# ReflowController_v1_3.net
KiCad netlist of a schematic drawn in EAGLE
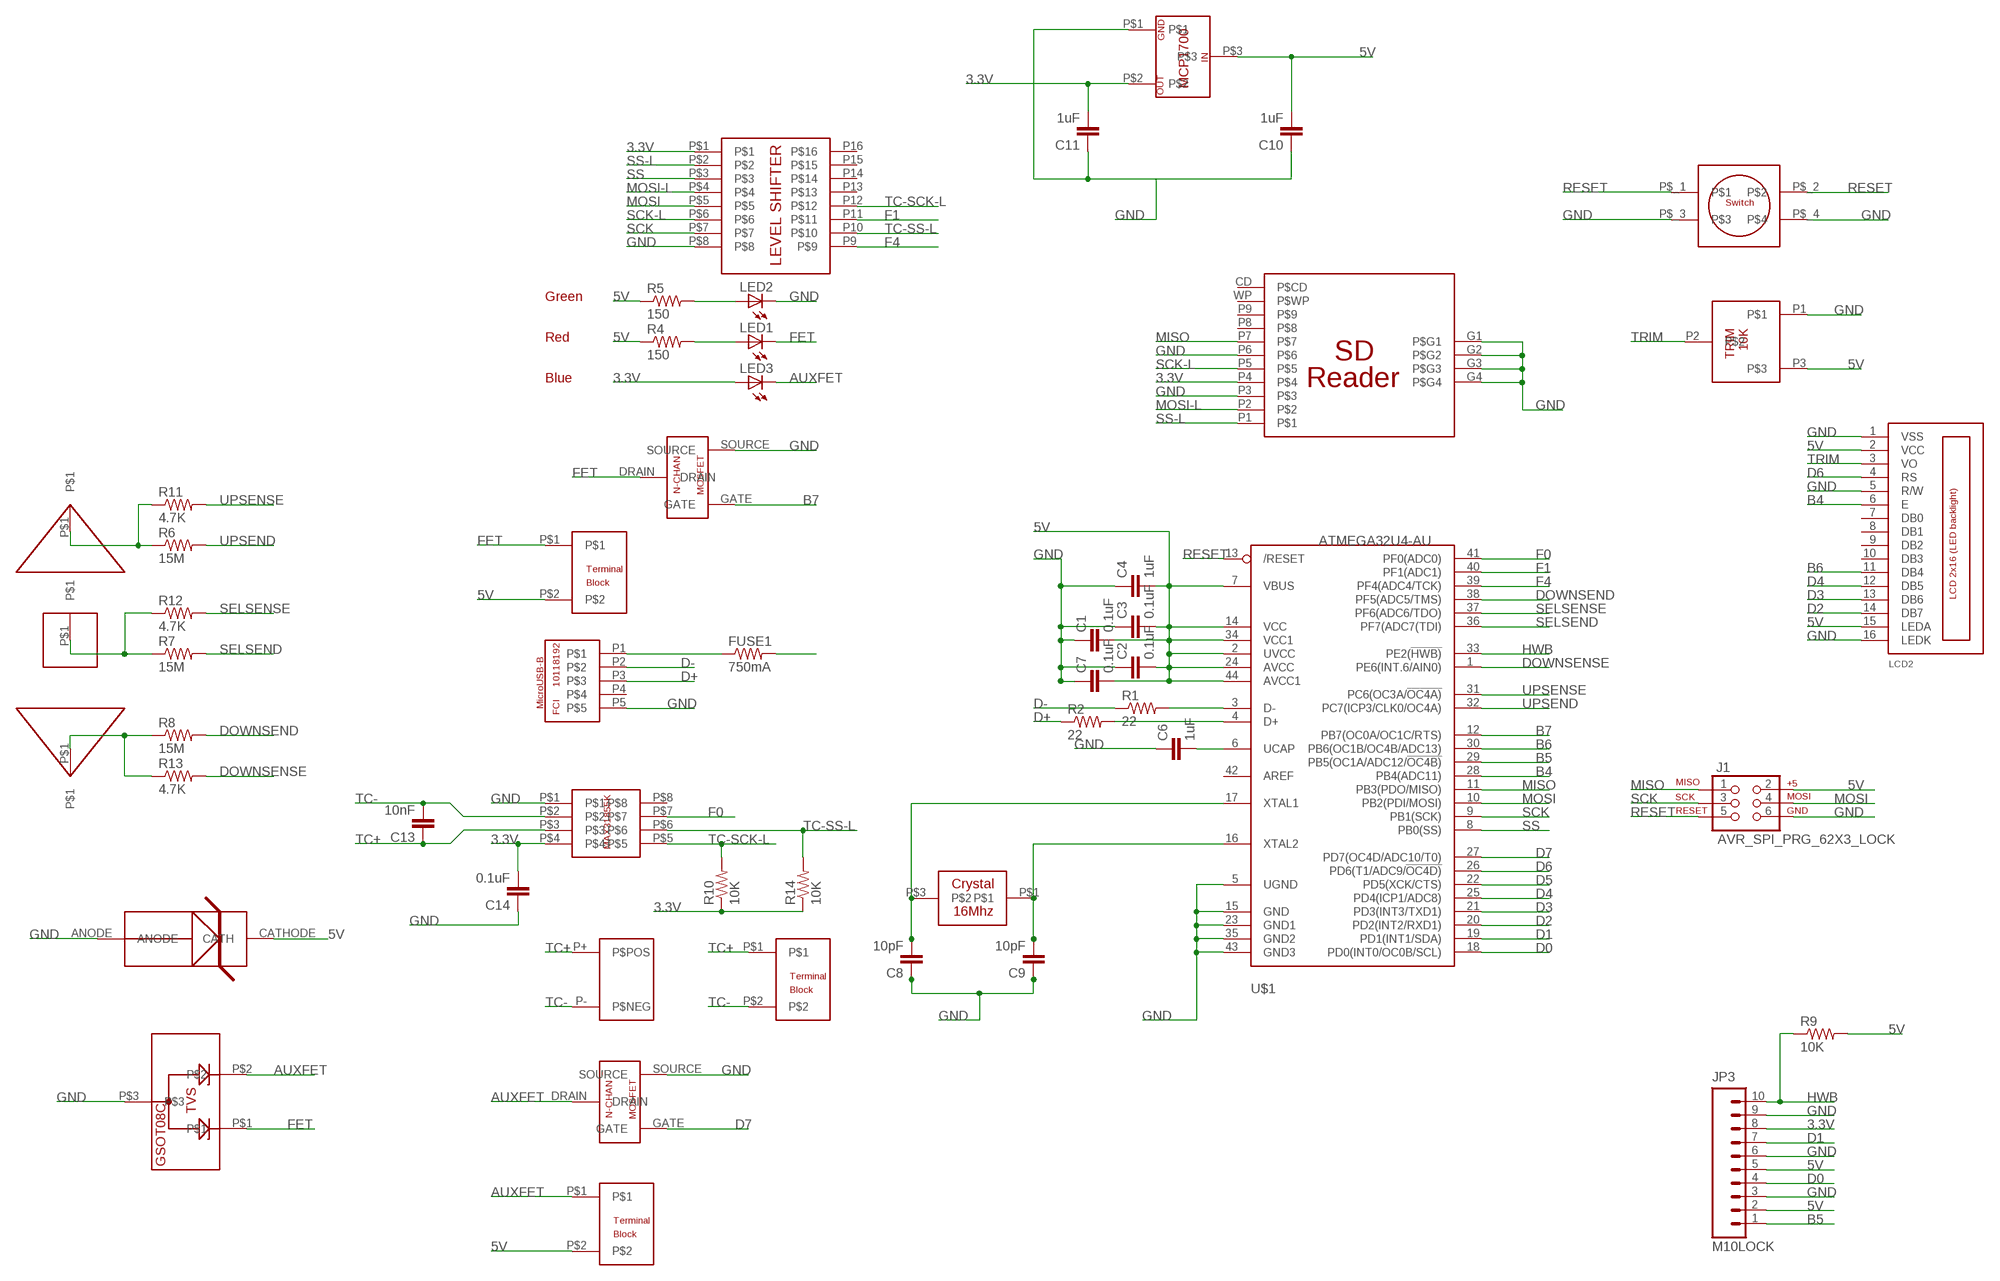
[diagram p0: schematic, sheet 1]

(export (version "E")
  (design (tool "Eeschema 10.0.6"))
  (components
    (comp (ref "C1")
      (value "0.1uF")
      (footprint "eagle-import:0603-CAP")
      (libsource (lib "eagle-import") (part "CAP0603-CAP"))
    )
    (comp (ref "C2")
      (value "0.1uF")
      (footprint "eagle-import:0603-CAP")
      (libsource (lib "eagle-import") (part "CAP0603-CAP"))
    )
    (comp (ref "C3")
      (value "0.1uF")
      (footprint "eagle-import:0603-CAP")
      (libsource (lib "eagle-import") (part "CAP0603-CAP"))
    )
    (comp (ref "C4")
      (value "1uF")
      (footprint "eagle-import:0603-CAP")
      (libsource (lib "eagle-import") (part "CAP0603-CAP"))
    )
    (comp (ref "C6")
      (value "1uF")
      (footprint "eagle-import:0603-CAP")
      (libsource (lib "eagle-import") (part "CAP0603-CAP"))
    )
    (comp (ref "C7")
      (value "0.1uF")
      (footprint "eagle-import:0603-CAP")
      (libsource (lib "eagle-import") (part "CAP0603-CAP"))
    )
    (comp (ref "C8")
      (value "10pF")
      (footprint "eagle-import:0603-CAP")
      (libsource (lib "eagle-import") (part "CAP0603-CAP"))
    )
    (comp (ref "C9")
      (value "10pF")
      (footprint "eagle-import:0603-CAP")
      (libsource (lib "eagle-import") (part "CAP0603-CAP"))
    )
    (comp (ref "C10")
      (value "1uF")
      (footprint "eagle-import:0603-CAP")
      (libsource (lib "eagle-import") (part "CAP0603-CAP"))
    )
    (comp (ref "C11")
      (value "1uF")
      (footprint "eagle-import:0603-CAP")
      (libsource (lib "eagle-import") (part "CAP0603-CAP"))
    )
    (comp (ref "C13")
      (value "10nF")
      (footprint "eagle-import:0603-CAP")
      (libsource (lib "eagle-import") (part "CAP0603-CAP"))
    )
    (comp (ref "C14")
      (value "0.1uF")
      (footprint "eagle-import:0603-CAP")
      (libsource (lib "eagle-import") (part "CAP0603-CAP"))
    )
    (comp (ref "FUSE1")
      (value "750mA")
      (footprint "eagle-import:0603-RES")
      (libsource (lib "eagle-import") (part "RESISTOR0603-RES"))
    )
    (comp (ref "J1")
      (value "AVR_SPI_PRG_62X3_LOCK")
      (footprint "eagle-import:2X3_LOCK")
      (libsource (lib "eagle-import") (part "AVR_SPI_PRG_62X3_LOCK"))
    )
    (comp (ref "JP3")
      (value "M10LOCK")
      (footprint "eagle-import:1X10_LOCK")
      (libsource (lib "eagle-import") (part "M10LOCK"))
    )
    (comp (ref "LCD2")
      (value "LCD_2X16_SIL")
      (footprint "eagle-import:HY-1602F")
      (libsource (lib "eagle-import") (part "LCD_2X16_SIL"))
    )
    (comp (ref "LED1")
      (value "LED0603")
      (footprint "eagle-import:LED-0603")
      (libsource (lib "eagle-import") (part "LED0603"))
    )
    (comp (ref "LED2")
      (value "LED0603")
      (footprint "eagle-import:LED-0603")
      (libsource (lib "eagle-import") (part "LED0603"))
    )
    (comp (ref "LED3")
      (value "LED0603")
      (footprint "eagle-import:LED-0603")
      (libsource (lib "eagle-import") (part "LED0603"))
    )
    (comp (ref "R1")
      (value "22")
      (footprint "eagle-import:0603-RES")
      (libsource (lib "eagle-import") (part "RESISTOR0603-RES"))
    )
    (comp (ref "R2")
      (value "22")
      (footprint "eagle-import:0603-RES")
      (libsource (lib "eagle-import") (part "RESISTOR0603-RES"))
    )
    (comp (ref "R4")
      (value "150")
      (footprint "eagle-import:0603-RES")
      (libsource (lib "eagle-import") (part "RESISTOR0603-RES"))
    )
    (comp (ref "R5")
      (value "150")
      (footprint "eagle-import:0603-RES")
      (libsource (lib "eagle-import") (part "RESISTOR0603-RES"))
    )
    (comp (ref "R6")
      (value "15M")
      (footprint "eagle-import:0603-RES")
      (libsource (lib "eagle-import") (part "RESISTOR0603-RES"))
    )
    (comp (ref "R7")
      (value "15M")
      (footprint "eagle-import:0603-RES")
      (libsource (lib "eagle-import") (part "RESISTOR0603-RES"))
    )
    (comp (ref "R8")
      (value "15M")
      (footprint "eagle-import:0603-RES")
      (libsource (lib "eagle-import") (part "RESISTOR0603-RES"))
    )
    (comp (ref "R9")
      (value "10K")
      (footprint "eagle-import:0603-RES")
      (libsource (lib "eagle-import") (part "RESISTOR0603-RES"))
    )
    (comp (ref "R10")
      (value "10K")
      (footprint "eagle-import:0603-RES")
      (libsource (lib "eagle-import") (part "RESISTOR0603-RES"))
    )
    (comp (ref "R11")
      (value "4.7K")
      (footprint "eagle-import:0603-RES")
      (libsource (lib "eagle-import") (part "RESISTOR0603-RES"))
    )
    (comp (ref "R12")
      (value "4.7K")
      (footprint "eagle-import:0603-RES")
      (libsource (lib "eagle-import") (part "RESISTOR0603-RES"))
    )
    (comp (ref "R13")
      (value "4.7K")
      (footprint "eagle-import:0603-RES")
      (libsource (lib "eagle-import") (part "RESISTOR0603-RES"))
    )
    (comp (ref "R14")
      (value "10K")
      (footprint "eagle-import:0603-RES")
      (libsource (lib "eagle-import") (part "RESISTOR0603-RES"))
    )
    (comp (ref "U$1")
      (value "ATMEGA32U4-AU")
      (footprint "eagle-import:TQFP44")
      (libsource (lib "eagle-import") (part "ATMEGA32U4-AU"))
    )
    (comp (ref "U$2")
      (value "16MHZ-CRYSTAL_NX3225GA-16.000M-STD-CRG-1")
      (footprint "eagle-import:16MHZ-CRYSTAL_NX3225GA-16.000M-STD-CRG-1")
      (libsource (lib "eagle-import") (part "16MHZ-CRYSTAL_NX3225GA-16.000M-STD-CRG-1"))
    )
    (comp (ref "U$3")
      (value "USB-B_10118192-0001LF")
      (footprint "eagle-import:USB-B_10118192-0001LF")
      (libsource (lib "eagle-import") (part "USB-B_10118192-0001LF"))
    )
    (comp (ref "U$4")
      (value "SDREADER_2041021-4")
      (footprint "eagle-import:SDREADER_2041021-4")
      (libsource (lib "eagle-import") (part "SDREADER_2041021-4"))
    )
    (comp (ref "U$5")
      (value "2POS_TERM_ED2748-ND")
      (footprint "eagle-import:2POS_TERM_ED2748-ND")
      (libsource (lib "eagle-import") (part "2POS_TERM_ED2748-ND"))
    )
    (comp (ref "U$6")
      (value "N-MOSFET630_DMG1012T-7DICT-ND")
      (footprint "eagle-import:N-MOSFET630_DMG1012T-7DICT-ND")
      (libsource (lib "eagle-import") (part "N-MOSFET630_DMG1012T-7DICT-ND"))
    )
    (comp (ref "U$7")
      (value "2POS_TERM_ED2748-ND")
      (footprint "eagle-import:2POS_TERM_ED2748-ND")
      (libsource (lib "eagle-import") (part "2POS_TERM_ED2748-ND"))
    )
    (comp (ref "U$8")
      (value "NXP_LVL_SHIFT_74HC4050D,653")
      (footprint "eagle-import:NXP_LVL_SHIFT_74HC4050D,653")
      (libsource (lib "eagle-import") (part "NXP_LVL_SHIFT_74HC4050D,653"))
    )
    (comp (ref "U$9")
      (value "MAX_TC_MAX31855KASA+")
      (footprint "eagle-import:MAX_TC_MAX31855KASA+")
      (libsource (lib "eagle-import") (part "MAX_TC_MAX31855KASA+"))
    )
    (comp (ref "U$10")
      (value "10K_TRIM_3362F-1-103LF")
      (footprint "eagle-import:10K_TRIM_3362F-1-103LF")
      (libsource (lib "eagle-import") (part "10K_TRIM_3362F-1-103LF"))
    )
    (comp (ref "U$11")
      (value "MCP1700__LDO")
      (footprint "eagle-import:MCP1700__LDO")
      (libsource (lib "eagle-import") (part "MCP1700__LDO"))
    )
    (comp (ref "U$12")
      (value "MOM-SWITCH-EG4620CT-ND")
      (footprint "eagle-import:MOM-SWITCH-EG4620CT-ND")
      (libsource (lib "eagle-import") (part "MOM-SWITCH-EG4620CT-ND"))
    )
    (comp (ref "U$13")
      (value "CAPTOUCH_ARROW")
      (footprint "eagle-import:CAPTOUCH_ARROW")
      (libsource (lib "eagle-import") (part "CAPTOUCH_ARROW"))
    )
    (comp (ref "U$14")
      (value "CAPTOUCH_ARROW")
      (footprint "eagle-import:CAPTOUCH_ARROW")
      (libsource (lib "eagle-import") (part "CAPTOUCH_ARROW"))
    )
    (comp (ref "U$15")
      (value "CAPTOUCH_SQUARE")
      (footprint "eagle-import:CAPTOUCH_SQUARE")
      (libsource (lib "eagle-import") (part "CAPTOUCH_SQUARE"))
    )
    (comp (ref "U$16")
      (value "N-MOSFET630_DMG1012T-7DICT-ND")
      (footprint "eagle-import:N-MOSFET630_DMG1012T-7DICT-ND")
      (libsource (lib "eagle-import") (part "N-MOSFET630_DMG1012T-7DICT-ND"))
    )
    (comp (ref "U$17")
      (value "2POS_TERM_ED2748-ND")
      (footprint "eagle-import:2POS_TERM_ED2748-ND")
      (libsource (lib "eagle-import") (part "2POS_TERM_ED2748-ND"))
    )
    (comp (ref "U$18")
      (value "TVS_DIODE_MATRIX_GSOT08C-GS08")
      (footprint "eagle-import:TVS_DIODE_MATRIX_GSOT08C-GS08")
      (libsource (lib "eagle-import") (part "TVS_DIODE_MATRIX_GSOT08C-GS08"))
    )
    (comp (ref "U$19")
      (value "TVS_DIODE_1CH_1SMB6.0AT3G")
      (footprint "eagle-import:TVS_DIODE_1CH_1SMB6.0AT3G")
      (libsource (lib "eagle-import") (part "TVS_DIODE_1CH_1SMB6.0AT3G"))
    )
    (comp (ref "U$20")
      (value "CUSTOM_K-TYPE")
      (footprint "eagle-import:CUSTOM_K-TYPE")
      (libsource (lib "eagle-import") (part "CUSTOM_K-TYPE"))
    )
  )
  (nets
    (net (code "1") (name "/3.3V") (class "Default")
      (node (ref "C11") (pin "2") (pinfunction "2_2") (pintype "passive"))
      (node (ref "C14") (pin "2") (pinfunction "2_2") (pintype "passive"))
      (node (ref "JP3") (pin "8") (pinfunction "8_8") (pintype "passive"))
      (node (ref "LED3") (pin "A") (pinfunction "A_A") (pintype "passive"))
      (node (ref "R10") (pin "1") (pinfunction "1_1") (pintype "passive"))
      (node (ref "R14") (pin "1") (pinfunction "1_1") (pintype "passive"))
      (node (ref "U$11") (pin "P$2") (pinfunction "P$2_P$2") (pintype "bidirectional"))
      (node (ref "U$4") (pin "P4") (pinfunction "P$4_P4") (pintype "bidirectional"))
      (node (ref "U$8") (pin "P$1") (pinfunction "P$1_P$1") (pintype "bidirectional"))
      (node (ref "U$9") (pin "P$4") (pinfunction "P$4_P$4") (pintype "bidirectional"))
    )
    (net (code "2") (name "/5V") (class "Default")
      (node (ref "C1") (pin "2") (pinfunction "2_2") (pintype "passive"))
      (node (ref "C10") (pin "2") (pinfunction "2_2") (pintype "passive"))
      (node (ref "C2") (pin "2") (pinfunction "2_2") (pintype "passive"))
      (node (ref "C3") (pin "2") (pinfunction "2_2") (pintype "passive"))
      (node (ref "C4") (pin "2") (pinfunction "2_2") (pintype "passive"))
      (node (ref "C7") (pin "2") (pinfunction "2_2") (pintype "passive"))
      (node (ref "FUSE1") (pin "2") (pinfunction "2_2") (pintype "passive"))
      (node (ref "J1") (pin "2") (pinfunction "2_2") (pintype "passive"))
      (node (ref "JP3") (pin "2") (pinfunction "2_2") (pintype "passive"))
      (node (ref "JP3") (pin "5") (pinfunction "5_5") (pintype "passive"))
      (node (ref "LCD2") (pin "15") (pinfunction "LEDA_15") (pintype "passive"))
      (node (ref "LCD2") (pin "2") (pinfunction "VCC_2") (pintype "power_in"))
      (node (ref "R4") (pin "1") (pinfunction "1_1") (pintype "passive"))
      (node (ref "R5") (pin "1") (pinfunction "1_1") (pintype "passive"))
      (node (ref "R9") (pin "2") (pinfunction "2_2") (pintype "passive"))
      (node (ref "U$1") (pin "14") (pinfunction "VCC_14") (pintype "bidirectional"))
      (node (ref "U$1") (pin "2") (pinfunction "UVCC_2") (pintype "bidirectional"))
      (node (ref "U$1") (pin "24") (pinfunction "AVCC_24") (pintype "bidirectional"))
      (node (ref "U$1") (pin "34") (pinfunction "VCC1_34") (pintype "bidirectional"))
      (node (ref "U$1") (pin "44") (pinfunction "AVCC1_44") (pintype "bidirectional"))
      (node (ref "U$1") (pin "7") (pinfunction "VBUS_7") (pintype "bidirectional"))
      (node (ref "U$10") (pin "P3") (pinfunction "P$3_P3") (pintype "bidirectional"))
      (node (ref "U$11") (pin "P$3") (pinfunction "P$3_P$3") (pintype "bidirectional"))
      (node (ref "U$17") (pin "P$2") (pinfunction "P$2_P$2") (pintype "bidirectional"))
      (node (ref "U$19") (pin "CATHODE") (pinfunction "CATH_CATHODE") (pintype "bidirectional"))
      (node (ref "U$5") (pin "P$2") (pinfunction "P$2_P$2") (pintype "bidirectional"))
    )
    (net (code "3") (name "/AUXFET") (class "Default")
      (node (ref "LED3") (pin "C") (pinfunction "C_C") (pintype "passive"))
      (node (ref "U$16") (pin "DRAIN") (pinfunction "DRAIN_DRAIN") (pintype "bidirectional"))
      (node (ref "U$17") (pin "P$1") (pinfunction "P$1_P$1") (pintype "bidirectional"))
      (node (ref "U$18") (pin "P$2") (pinfunction "P$2_P$2") (pintype "bidirectional"))
    )
    (net (code "4") (name "/B4") (class "Default")
      (node (ref "LCD2") (pin "6") (pinfunction "E_6") (pintype "input"))
      (node (ref "U$1") (pin "28") (pinfunction "PB4(ADC11)_28") (pintype "bidirectional"))
    )
    (net (code "5") (name "/B5") (class "Default")
      (node (ref "JP3") (pin "1") (pinfunction "1_1") (pintype "passive"))
      (node (ref "U$1") (pin "29") (pinfunction "PB5(OC1A/ADC12/~{OC4B})_29") (pintype "bidirectional"))
    )
    (net (code "6") (name "/B6") (class "Default")
      (node (ref "LCD2") (pin "11") (pinfunction "DB4_11") (pintype "bidirectional"))
      (node (ref "U$1") (pin "30") (pinfunction "PB6(OC1B/OC4B/ADC13)_30") (pintype "bidirectional"))
    )
    (net (code "7") (name "/B7") (class "Default")
      (node (ref "U$1") (pin "12") (pinfunction "PB7(OC0A/OC1C/RTS)_12") (pintype "bidirectional"))
      (node (ref "U$6") (pin "GATE") (pinfunction "GATE_GATE") (pintype "bidirectional"))
    )
    (net (code "8") (name "/D+") (class "Default")
      (node (ref "R2") (pin "1") (pinfunction "1_1") (pintype "passive"))
      (node (ref "U$3") (pin "P3") (pinfunction "P$3_P3") (pintype "bidirectional"))
    )
    (net (code "9") (name "/D-") (class "Default")
      (node (ref "R1") (pin "1") (pinfunction "1_1") (pintype "passive"))
      (node (ref "U$3") (pin "P2") (pinfunction "P$2_P2") (pintype "bidirectional"))
    )
    (net (code "10") (name "/D0") (class "Default")
      (node (ref "JP3") (pin "4") (pinfunction "4_4") (pintype "passive"))
      (node (ref "U$1") (pin "18") (pinfunction "PD0(INT0/OC0B/SCL)_18") (pintype "bidirectional"))
    )
    (net (code "11") (name "/D1") (class "Default")
      (node (ref "JP3") (pin "7") (pinfunction "7_7") (pintype "passive"))
      (node (ref "U$1") (pin "19") (pinfunction "PD1(INT1/SDA)_19") (pintype "bidirectional"))
    )
    (net (code "12") (name "/D2") (class "Default")
      (node (ref "LCD2") (pin "14") (pinfunction "DB7_14") (pintype "bidirectional"))
      (node (ref "U$1") (pin "20") (pinfunction "PD2(INT2/RXD1)_20") (pintype "bidirectional"))
    )
    (net (code "13") (name "/D3") (class "Default")
      (node (ref "LCD2") (pin "13") (pinfunction "DB6_13") (pintype "bidirectional"))
      (node (ref "U$1") (pin "21") (pinfunction "PD3(INT3/TXD1)_21") (pintype "bidirectional"))
    )
    (net (code "14") (name "/D4") (class "Default")
      (node (ref "LCD2") (pin "12") (pinfunction "DB5_12") (pintype "bidirectional"))
      (node (ref "U$1") (pin "25") (pinfunction "PD4(ICP1/ADC8)_25") (pintype "bidirectional"))
    )
    (net (code "15") (name "/D5") (class "Default")
      (node (ref "U$1") (pin "22") (pinfunction "PD5(XCK/CTS)_22") (pintype "bidirectional"))
    )
    (net (code "16") (name "/D6") (class "Default")
      (node (ref "LCD2") (pin "4") (pinfunction "RS_4") (pintype "input"))
      (node (ref "U$1") (pin "26") (pinfunction "PD6(T1/ADC9/~{OC4D})_26") (pintype "bidirectional"))
    )
    (net (code "17") (name "/D7") (class "Default")
      (node (ref "U$1") (pin "27") (pinfunction "PD7(OC4D/ADC10/T0)_27") (pintype "bidirectional"))
      (node (ref "U$16") (pin "GATE") (pinfunction "GATE_GATE") (pintype "bidirectional"))
    )
    (net (code "18") (name "/DOWNSEND") (class "Default")
      (node (ref "R8") (pin "2") (pinfunction "2_2") (pintype "passive"))
      (node (ref "U$1") (pin "38") (pinfunction "PF5(ADC5/TMS)_38") (pintype "bidirectional"))
    )
    (net (code "19") (name "/DOWNSENSE") (class "Default")
      (node (ref "R13") (pin "2") (pinfunction "2_2") (pintype "passive"))
      (node (ref "U$1") (pin "1") (pinfunction "PE6(INT.6/AIN0)_1") (pintype "bidirectional"))
    )
    (net (code "20") (name "/F0") (class "Default")
      (node (ref "U$1") (pin "41") (pinfunction "PF0(ADC0)_41") (pintype "bidirectional"))
      (node (ref "U$9") (pin "P$7") (pinfunction "P$7_P$7") (pintype "bidirectional"))
    )
    (net (code "21") (name "/F1") (class "Default")
      (node (ref "U$1") (pin "40") (pinfunction "PF1(ADC1)_40") (pintype "bidirectional"))
      (node (ref "U$8") (pin "P11") (pinfunction "P$11_P11") (pintype "bidirectional"))
    )
    (net (code "22") (name "/F4") (class "Default")
      (node (ref "U$1") (pin "39") (pinfunction "PF4(ADC4/TCK)_39") (pintype "bidirectional"))
      (node (ref "U$8") (pin "P9") (pinfunction "P$9_P9") (pintype "bidirectional"))
    )
    (net (code "23") (name "/FET") (class "Default")
      (node (ref "LED1") (pin "C") (pinfunction "C_C") (pintype "passive"))
      (node (ref "U$18") (pin "P$1") (pinfunction "P$1_P$1") (pintype "bidirectional"))
      (node (ref "U$5") (pin "P$1") (pinfunction "P$1_P$1") (pintype "bidirectional"))
      (node (ref "U$6") (pin "DRAIN") (pinfunction "DRAIN_DRAIN") (pintype "bidirectional"))
    )
    (net (code "24") (name "/GND") (class "Default")
      (node (ref "C1") (pin "1") (pinfunction "1_1") (pintype "passive"))
      (node (ref "C10") (pin "1") (pinfunction "1_1") (pintype "passive"))
      (node (ref "C11") (pin "1") (pinfunction "1_1") (pintype "passive"))
      (node (ref "C14") (pin "1") (pinfunction "1_1") (pintype "passive"))
      (node (ref "C2") (pin "1") (pinfunction "1_1") (pintype "passive"))
      (node (ref "C3") (pin "1") (pinfunction "1_1") (pintype "passive"))
      (node (ref "C4") (pin "1") (pinfunction "1_1") (pintype "passive"))
      (node (ref "C6") (pin "1") (pinfunction "1_1") (pintype "passive"))
      (node (ref "C7") (pin "1") (pinfunction "1_1") (pintype "passive"))
      (node (ref "C8") (pin "1") (pinfunction "1_1") (pintype "passive"))
      (node (ref "C9") (pin "1") (pinfunction "1_1") (pintype "passive"))
      (node (ref "J1") (pin "6") (pinfunction "6_6") (pintype "passive"))
      (node (ref "JP3") (pin "3") (pinfunction "3_3") (pintype "passive"))
      (node (ref "JP3") (pin "6") (pinfunction "6_6") (pintype "passive"))
      (node (ref "JP3") (pin "9") (pinfunction "9_9") (pintype "passive"))
      (node (ref "LCD2") (pin "1") (pinfunction "VSS_1") (pintype "power_in"))
      (node (ref "LCD2") (pin "16") (pinfunction "LEDK_16") (pintype "passive"))
      (node (ref "LCD2") (pin "5") (pinfunction "R/W_5") (pintype "input"))
      (node (ref "LED2") (pin "C") (pinfunction "C_C") (pintype "passive"))
      (node (ref "U$1") (pin "15") (pinfunction "GND_15") (pintype "bidirectional"))
      (node (ref "U$1") (pin "23") (pinfunction "GND1_23") (pintype "bidirectional"))
      (node (ref "U$1") (pin "35") (pinfunction "GND2_35") (pintype "bidirectional"))
      (node (ref "U$1") (pin "43") (pinfunction "GND3_43") (pintype "bidirectional"))
      (node (ref "U$1") (pin "5") (pinfunction "UGND_5") (pintype "bidirectional"))
      (node (ref "U$10") (pin "P1") (pinfunction "P$1_P1") (pintype "bidirectional"))
      (node (ref "U$11") (pin "P$1") (pinfunction "P$1_P$1") (pintype "bidirectional"))
      (node (ref "U$12") (pin "P$_3") (pinfunction "P$3_P$_3") (pintype "bidirectional"))
      (node (ref "U$12") (pin "P$_4") (pinfunction "P$4_P$_4") (pintype "bidirectional"))
      (node (ref "U$16") (pin "SOURCE") (pinfunction "SOURCE_SOURCE") (pintype "bidirectional"))
      (node (ref "U$18") (pin "P$3") (pinfunction "P$3_P$3") (pintype "bidirectional"))
      (node (ref "U$19") (pin "ANODE") (pinfunction "ANODE_ANODE") (pintype "bidirectional"))
      (node (ref "U$3") (pin "P5") (pinfunction "P$5_P5") (pintype "bidirectional"))
      (node (ref "U$4") (pin "G1") (pinfunction "P$G1_G1") (pintype "bidirectional"))
      (node (ref "U$4") (pin "G2") (pinfunction "P$G2_G2") (pintype "bidirectional"))
      (node (ref "U$4") (pin "G3") (pinfunction "P$G3_G3") (pintype "bidirectional"))
      (node (ref "U$4") (pin "G4") (pinfunction "P$G4_G4") (pintype "bidirectional"))
      (node (ref "U$4") (pin "P3") (pinfunction "P$3_P3") (pintype "bidirectional"))
      (node (ref "U$4") (pin "P6") (pinfunction "P$6_P6") (pintype "bidirectional"))
      (node (ref "U$6") (pin "SOURCE") (pinfunction "SOURCE_SOURCE") (pintype "bidirectional"))
      (node (ref "U$8") (pin "P$8") (pinfunction "P$8_P$8") (pintype "bidirectional"))
      (node (ref "U$9") (pin "P$1") (pinfunction "P$1_P$1") (pintype "bidirectional"))
    )
    (net (code "25") (name "/HWB") (class "Default")
      (node (ref "JP3") (pin "10") (pinfunction "10_10") (pintype "passive"))
      (node (ref "R9") (pin "1") (pinfunction "1_1") (pintype "passive"))
      (node (ref "U$1") (pin "33") (pinfunction "PE2(~{HWB})_33") (pintype "bidirectional"))
    )
    (net (code "26") (name "/MISO") (class "Default")
      (node (ref "J1") (pin "1") (pinfunction "1_1") (pintype "passive"))
      (node (ref "U$1") (pin "11") (pinfunction "PB3(PDO/MISO)_11") (pintype "bidirectional"))
      (node (ref "U$4") (pin "P7") (pinfunction "P$7_P7") (pintype "bidirectional"))
    )
    (net (code "27") (name "/MOSI") (class "Default")
      (node (ref "J1") (pin "4") (pinfunction "4_4") (pintype "passive"))
      (node (ref "U$1") (pin "10") (pinfunction "PB2(PDI/MOSI)_10") (pintype "bidirectional"))
      (node (ref "U$8") (pin "P$5") (pinfunction "P$5_P$5") (pintype "bidirectional"))
    )
    (net (code "28") (name "/MOSI-L") (class "Default")
      (node (ref "U$4") (pin "P2") (pinfunction "P$2_P2") (pintype "bidirectional"))
      (node (ref "U$8") (pin "P$4") (pinfunction "P$4_P$4") (pintype "bidirectional"))
    )
    (net (code "29") (name "/RESET") (class "Default")
      (node (ref "J1") (pin "5") (pinfunction "5_5") (pintype "passive"))
      (node (ref "U$1") (pin "13") (pinfunction "/RESET_13") (pintype "bidirectional"))
      (node (ref "U$12") (pin "P$_1") (pinfunction "P$1_P$_1") (pintype "bidirectional"))
      (node (ref "U$12") (pin "P$_2") (pinfunction "P$2_P$_2") (pintype "bidirectional"))
    )
    (net (code "30") (name "/SCK") (class "Default")
      (node (ref "J1") (pin "3") (pinfunction "3_3") (pintype "passive"))
      (node (ref "U$1") (pin "9") (pinfunction "PB1(SCK)_9") (pintype "bidirectional"))
      (node (ref "U$8") (pin "P$7") (pinfunction "P$7_P$7") (pintype "bidirectional"))
    )
    (net (code "31") (name "/SCK-L") (class "Default")
      (node (ref "U$4") (pin "P5") (pinfunction "P$5_P5") (pintype "bidirectional"))
      (node (ref "U$8") (pin "P$6") (pinfunction "P$6_P$6") (pintype "bidirectional"))
    )
    (net (code "32") (name "/SELSEND") (class "Default")
      (node (ref "R7") (pin "2") (pinfunction "2_2") (pintype "passive"))
      (node (ref "U$1") (pin "36") (pinfunction "PF7(ADC7(TDI)_36") (pintype "bidirectional"))
    )
    (net (code "33") (name "/SELSENSE") (class "Default")
      (node (ref "R12") (pin "2") (pinfunction "2_2") (pintype "passive"))
      (node (ref "U$1") (pin "37") (pinfunction "PF6(ADC6/TDO)_37") (pintype "bidirectional"))
    )
    (net (code "34") (name "/SS") (class "Default")
      (node (ref "U$1") (pin "8") (pinfunction "PB0(SS)_8") (pintype "bidirectional"))
      (node (ref "U$8") (pin "P$3") (pinfunction "P$3_P$3") (pintype "bidirectional"))
    )
    (net (code "35") (name "/SS-L") (class "Default")
      (node (ref "U$4") (pin "P1") (pinfunction "P$1_P1") (pintype "bidirectional"))
      (node (ref "U$8") (pin "P$2") (pinfunction "P$2_P$2") (pintype "bidirectional"))
    )
    (net (code "36") (name "/TC+") (class "Default")
      (node (ref "C13") (pin "1") (pinfunction "1_1") (pintype "passive"))
      (node (ref "U$20") (pin "P+") (pinfunction "P$POS_P+") (pintype "bidirectional"))
      (node (ref "U$7") (pin "P$1") (pinfunction "P$1_P$1") (pintype "bidirectional"))
      (node (ref "U$9") (pin "P$3") (pinfunction "P$3_P$3") (pintype "bidirectional"))
    )
    (net (code "37") (name "/TC-") (class "Default")
      (node (ref "C13") (pin "2") (pinfunction "2_2") (pintype "passive"))
      (node (ref "U$20") (pin "P-") (pinfunction "P$NEG_P-") (pintype "bidirectional"))
      (node (ref "U$7") (pin "P$2") (pinfunction "P$2_P$2") (pintype "bidirectional"))
      (node (ref "U$9") (pin "P$2") (pinfunction "P$2_P$2") (pintype "bidirectional"))
    )
    (net (code "38") (name "/TC-SCK-L") (class "Default")
      (node (ref "R10") (pin "2") (pinfunction "2_2") (pintype "passive"))
      (node (ref "U$8") (pin "P12") (pinfunction "P$12_P12") (pintype "bidirectional"))
      (node (ref "U$9") (pin "P$5") (pinfunction "P$5_P$5") (pintype "bidirectional"))
    )
    (net (code "39") (name "/TC-SS-L") (class "Default")
      (node (ref "R14") (pin "2") (pinfunction "2_2") (pintype "passive"))
      (node (ref "U$8") (pin "P10") (pinfunction "P$10_P10") (pintype "bidirectional"))
      (node (ref "U$9") (pin "P$6") (pinfunction "P$6_P$6") (pintype "bidirectional"))
    )
    (net (code "40") (name "/TRIM") (class "Default")
      (node (ref "LCD2") (pin "3") (pinfunction "VO_3") (pintype "input"))
      (node (ref "U$10") (pin "P2") (pinfunction "P$2_P2") (pintype "bidirectional"))
    )
    (net (code "41") (name "/UPSEND") (class "Default")
      (node (ref "R6") (pin "2") (pinfunction "2_2") (pintype "passive"))
      (node (ref "U$1") (pin "32") (pinfunction "PC7(ICP3/CLK0/OC4A)_32") (pintype "bidirectional"))
    )
    (net (code "42") (name "/UPSENSE") (class "Default")
      (node (ref "R11") (pin "2") (pinfunction "2_2") (pintype "passive"))
      (node (ref "U$1") (pin "31") (pinfunction "PC6(OC3A/~{OC4A})_31") (pintype "bidirectional"))
    )
    (net (code "43") (name "Net-(LED1-PadA)") (class "Default")
      (node (ref "LED1") (pin "A") (pinfunction "A_A") (pintype "passive"))
      (node (ref "R4") (pin "2") (pinfunction "2_2") (pintype "passive"))
    )
    (net (code "44") (name "Net-(LED2-PadA)") (class "Default")
      (node (ref "LED2") (pin "A") (pinfunction "A_A") (pintype "passive"))
      (node (ref "R5") (pin "2") (pinfunction "2_2") (pintype "passive"))
    )
    (net (code "45") (name "Net-(R11-Pad1)") (class "Default")
      (node (ref "R11") (pin "1") (pinfunction "1_1") (pintype "passive"))
      (node (ref "R6") (pin "1") (pinfunction "1_1") (pintype "passive"))
      (node (ref "U$13") (pin "P$1") (pinfunction "P$1_P$1") (pintype "bidirectional"))
    )
    (net (code "46") (name "Net-(R12-Pad1)") (class "Default")
      (node (ref "R12") (pin "1") (pinfunction "1_1") (pintype "passive"))
      (node (ref "R7") (pin "1") (pinfunction "1_1") (pintype "passive"))
      (node (ref "U$15") (pin "P$1") (pinfunction "P$1_P$1") (pintype "bidirectional"))
    )
    (net (code "47") (name "Net-(R13-Pad1)") (class "Default")
      (node (ref "R13") (pin "1") (pinfunction "1_1") (pintype "passive"))
      (node (ref "R8") (pin "1") (pinfunction "1_1") (pintype "passive"))
      (node (ref "U$14") (pin "P$1") (pinfunction "P$1_P$1") (pintype "bidirectional"))
    )
    (net (code "48") (name "Net-(U$1-D+)") (class "Default")
      (node (ref "R2") (pin "2") (pinfunction "2_2") (pintype "passive"))
      (node (ref "U$1") (pin "4") (pinfunction "D+_4") (pintype "bidirectional"))
    )
    (net (code "49") (name "Net-(U$1-D-)") (class "Default")
      (node (ref "R1") (pin "2") (pinfunction "2_2") (pintype "passive"))
      (node (ref "U$1") (pin "3") (pinfunction "D-_3") (pintype "bidirectional"))
    )
    (net (code "50") (name "Net-(U$1-UCAP)") (class "Default")
      (node (ref "C6") (pin "2") (pinfunction "2_2") (pintype "passive"))
      (node (ref "U$1") (pin "6") (pinfunction "UCAP_6") (pintype "bidirectional"))
    )
    (net (code "51") (name "Net-(U$1-XTAL1)") (class "Default")
      (node (ref "C8") (pin "2") (pinfunction "2_2") (pintype "passive"))
      (node (ref "U$1") (pin "17") (pinfunction "XTAL1_17") (pintype "bidirectional"))
      (node (ref "U$2") (pin "P$3") (pinfunction "P$2_P$3") (pintype "bidirectional"))
    )
    (net (code "52") (name "Net-(U$1-XTAL2)") (class "Default")
      (node (ref "C9") (pin "2") (pinfunction "2_2") (pintype "passive"))
      (node (ref "U$1") (pin "16") (pinfunction "XTAL2_16") (pintype "bidirectional"))
      (node (ref "U$2") (pin "P$1") (pinfunction "P$1_P$1") (pintype "bidirectional"))
    )
    (net (code "53") (name "Net-(U$3-P$1)") (class "Default")
      (node (ref "FUSE1") (pin "1") (pinfunction "1_1") (pintype "passive"))
      (node (ref "U$3") (pin "P1") (pinfunction "P$1_P1") (pintype "bidirectional"))
    )
    (net (code "54") (name "unconnected-(LCD2-DB0-Pad7)") (class "Default")
      (node (ref "LCD2") (pin "7") (pinfunction "DB0_7") (pintype "bidirectional"))
    )
    (net (code "55") (name "unconnected-(LCD2-DB1-Pad8)") (class "Default")
      (node (ref "LCD2") (pin "8") (pinfunction "DB1_8") (pintype "bidirectional"))
    )
    (net (code "56") (name "unconnected-(LCD2-DB2-Pad9)") (class "Default")
      (node (ref "LCD2") (pin "9") (pinfunction "DB2_9") (pintype "bidirectional"))
    )
    (net (code "57") (name "unconnected-(LCD2-DB3-Pad10)") (class "Default")
      (node (ref "LCD2") (pin "10") (pinfunction "DB3_10") (pintype "bidirectional"))
    )
    (net (code "58") (name "unconnected-(U$1-AREF-Pad42)") (class "Default")
      (node (ref "U$1") (pin "42") (pinfunction "AREF_42") (pintype "bidirectional"))
    )
    (net (code "59") (name "unconnected-(U$3-P$4-PadP4)") (class "Default")
      (node (ref "U$3") (pin "P4") (pinfunction "P$4_P4") (pintype "bidirectional"))
    )
    (net (code "60") (name "unconnected-(U$4-P$8-PadP8)") (class "Default")
      (node (ref "U$4") (pin "P8") (pinfunction "P$8_P8") (pintype "bidirectional"))
    )
    (net (code "61") (name "unconnected-(U$4-P$9-PadP9)") (class "Default")
      (node (ref "U$4") (pin "P9") (pinfunction "P$9_P9") (pintype "bidirectional"))
    )
    (net (code "62") (name "unconnected-(U$4-P$CD-PadCD)") (class "Default")
      (node (ref "U$4") (pin "CD") (pinfunction "P$CD_CD") (pintype "bidirectional"))
    )
    (net (code "63") (name "unconnected-(U$4-P$WP-PadWP)") (class "Default")
      (node (ref "U$4") (pin "WP") (pinfunction "P$WP_WP") (pintype "bidirectional"))
    )
    (net (code "64") (name "unconnected-(U$8-P$13-PadP13)") (class "Default")
      (node (ref "U$8") (pin "P13") (pinfunction "P$13_P13") (pintype "bidirectional"))
    )
    (net (code "65") (name "unconnected-(U$8-P$14-PadP14)") (class "Default")
      (node (ref "U$8") (pin "P14") (pinfunction "P$14_P14") (pintype "bidirectional"))
    )
    (net (code "66") (name "unconnected-(U$8-P$15-PadP15)") (class "Default")
      (node (ref "U$8") (pin "P15") (pinfunction "P$15_P15") (pintype "bidirectional"))
    )
    (net (code "67") (name "unconnected-(U$8-P$16-PadP16)") (class "Default")
      (node (ref "U$8") (pin "P16") (pinfunction "P$16_P16") (pintype "bidirectional"))
    )
    (net (code "68") (name "unconnected-(U$9-PadP$8)") (class "Default")
      (node (ref "U$9") (pin "P$8") (pinfunction "P$8_P$8") (pintype "bidirectional"))
    )
  )
)
